# rs232_adapter.net
KiCad netlist of a schematic drawn in EAGLE
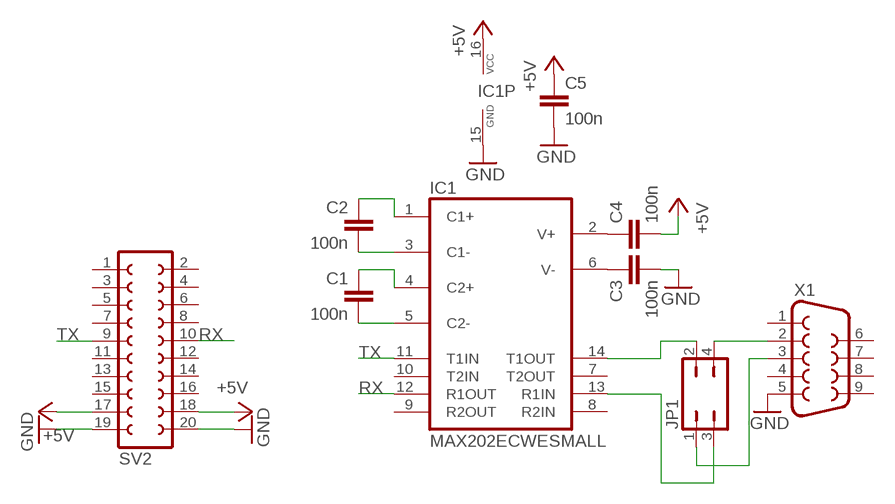
[diagram p0: schematic, sheet 1]

(export (version "E")
  (design (tool "Eeschema 10.0.6"))
  (components
    (comp (ref "C1")
      (value "100n")
      (footprint "eagle-import:C0805")
      (libsource (lib "eagle-import") (part "C-EUC0805"))
    )
    (comp (ref "C2")
      (value "100n")
      (footprint "eagle-import:C0805")
      (libsource (lib "eagle-import") (part "C-EUC0805"))
    )
    (comp (ref "C3")
      (value "100n")
      (footprint "eagle-import:C0805")
      (libsource (lib "eagle-import") (part "C-EUC0805"))
    )
    (comp (ref "C4")
      (value "100n")
      (footprint "eagle-import:C0805")
      (libsource (lib "eagle-import") (part "C-EUC0805"))
    )
    (comp (ref "C5")
      (value "100n")
      (footprint "eagle-import:C0805")
      (libsource (lib "eagle-import") (part "C-EUC0805"))
    )
    (comp (ref "IC1")
      (value "MAX202ECWESMALL")
      (footprint "eagle-import:SO16")
      (libsource (lib "eagle-import") (part "MAX202ECWESMALL"))
    )
    (comp (ref "JP1")
      (value "JP2Q")
      (footprint "eagle-import:JP2Q")
      (libsource (lib "eagle-import") (part "JP2Q"))
    )
    (comp (ref "SV2")
      (value "FE10-2")
      (footprint "eagle-import:FE10-2")
      (libsource (lib "eagle-import") (part "FE10-2"))
    )
    (comp (ref "X1")
      (value "F09HP")
      (footprint "eagle-import:F09HP")
      (libsource (lib "eagle-import") (part "F09HP"))
    )
  )
  (nets
    (net (code "1") (name "+5V") (class "Default")
      (node (ref "C4") (pin "2") (pinfunction "2_2") (pintype "passive"))
      (node (ref "C5") (pin "1") (pinfunction "1_1") (pintype "passive"))
      (node (ref "IC1") (pin "16") (pinfunction "VCC_16") (pintype "power_in"))
      (node (ref "SV2") (pin "17") (pinfunction "17_17") (pintype "passive"))
      (node (ref "SV2") (pin "18") (pinfunction "18_18") (pintype "passive"))
    )
    (net (code "2") (name "/RX") (class "Default")
      (node (ref "IC1") (pin "12") (pinfunction "R1OUT_12") (pintype "output"))
      (node (ref "SV2") (pin "10") (pinfunction "10_10") (pintype "passive"))
    )
    (net (code "3") (name "/TX") (class "Default")
      (node (ref "IC1") (pin "11") (pinfunction "T1IN_11") (pintype "input"))
      (node (ref "SV2") (pin "9") (pinfunction "9_9") (pintype "passive"))
    )
    (net (code "4") (name "GND") (class "Default")
      (node (ref "C3") (pin "2") (pinfunction "2_2") (pintype "passive"))
      (node (ref "C5") (pin "2") (pinfunction "2_2") (pintype "passive"))
      (node (ref "IC1") (pin "15") (pinfunction "GND_15") (pintype "power_in"))
      (node (ref "SV2") (pin "19") (pinfunction "19_19") (pintype "passive"))
      (node (ref "SV2") (pin "20") (pinfunction "20_20") (pintype "passive"))
      (node (ref "X1") (pin "5") (pinfunction "5_5") (pintype "passive"))
    )
    (net (code "5") (name "Net-(IC1A-C1+)") (class "Default")
      (node (ref "C2") (pin "1") (pinfunction "1_1") (pintype "passive"))
      (node (ref "IC1") (pin "1") (pinfunction "C1+_1") (pintype "bidirectional"))
    )
    (net (code "6") (name "Net-(IC1A-C1-)") (class "Default")
      (node (ref "C2") (pin "2") (pinfunction "2_2") (pintype "passive"))
      (node (ref "IC1") (pin "3") (pinfunction "C1-_3") (pintype "bidirectional"))
    )
    (net (code "7") (name "Net-(IC1A-C2+)") (class "Default")
      (node (ref "C1") (pin "1") (pinfunction "1_1") (pintype "passive"))
      (node (ref "IC1") (pin "4") (pinfunction "C2+_4") (pintype "bidirectional"))
    )
    (net (code "8") (name "Net-(IC1A-C2-)") (class "Default")
      (node (ref "C1") (pin "2") (pinfunction "2_2") (pintype "passive"))
      (node (ref "IC1") (pin "5") (pinfunction "C2-_5") (pintype "bidirectional"))
    )
    (net (code "9") (name "Net-(IC1A-R1IN)") (class "Default")
      (node (ref "IC1") (pin "13") (pinfunction "R1IN_13") (pintype "input"))
      (node (ref "JP1") (pin "3") (pinfunction "3_3") (pintype "passive"))
    )
    (net (code "10") (name "Net-(IC1A-T1OUT)") (class "Default")
      (node (ref "IC1") (pin "14") (pinfunction "T1OUT_14") (pintype "output"))
      (node (ref "JP1") (pin "2") (pinfunction "2_2") (pintype "passive"))
    )
    (net (code "11") (name "Net-(IC1A-V+)") (class "Default")
      (node (ref "C4") (pin "1") (pinfunction "1_1") (pintype "passive"))
      (node (ref "IC1") (pin "2") (pinfunction "V+_2") (pintype "bidirectional"))
    )
    (net (code "12") (name "Net-(IC1A-V-)") (class "Default")
      (node (ref "C3") (pin "1") (pinfunction "1_1") (pintype "passive"))
      (node (ref "IC1") (pin "6") (pinfunction "V-_6") (pintype "bidirectional"))
    )
    (net (code "13") (name "Net-(JP1-Pad1)") (class "Default")
      (node (ref "JP1") (pin "1") (pinfunction "1_1") (pintype "passive"))
      (node (ref "X1") (pin "3") (pinfunction "3_3") (pintype "passive"))
    )
    (net (code "14") (name "Net-(JP1-Pad4)") (class "Default")
      (node (ref "JP1") (pin "4") (pinfunction "4_4") (pintype "passive"))
      (node (ref "X1") (pin "2") (pinfunction "2_2") (pintype "passive"))
    )
    (net (code "15") (name "unconnected-(IC1A-R2IN-Pad8)") (class "Default")
      (node (ref "IC1") (pin "8") (pinfunction "R2IN_8") (pintype "input"))
    )
    (net (code "16") (name "unconnected-(IC1A-R2OUT-Pad9)") (class "Default")
      (node (ref "IC1") (pin "9") (pinfunction "R2OUT_9") (pintype "output"))
    )
    (net (code "17") (name "unconnected-(IC1A-T2IN-Pad10)") (class "Default")
      (node (ref "IC1") (pin "10") (pinfunction "T2IN_10") (pintype "input"))
    )
    (net (code "18") (name "unconnected-(IC1A-T2OUT-Pad7)") (class "Default")
      (node (ref "IC1") (pin "7") (pinfunction "T2OUT_7") (pintype "output"))
    )
    (net (code "19") (name "unconnected-(SV2-Pad1)") (class "Default")
      (node (ref "SV2") (pin "1") (pinfunction "1_1") (pintype "passive"))
    )
    (net (code "20") (name "unconnected-(SV2-Pad2)") (class "Default")
      (node (ref "SV2") (pin "2") (pinfunction "2_2") (pintype "passive"))
    )
    (net (code "21") (name "unconnected-(SV2-Pad3)") (class "Default")
      (node (ref "SV2") (pin "3") (pinfunction "3_3") (pintype "passive"))
    )
    (net (code "22") (name "unconnected-(SV2-Pad4)") (class "Default")
      (node (ref "SV2") (pin "4") (pinfunction "4_4") (pintype "passive"))
    )
    (net (code "23") (name "unconnected-(SV2-Pad5)") (class "Default")
      (node (ref "SV2") (pin "5") (pinfunction "5_5") (pintype "passive"))
    )
    (net (code "24") (name "unconnected-(SV2-Pad6)") (class "Default")
      (node (ref "SV2") (pin "6") (pinfunction "6_6") (pintype "passive"))
    )
    (net (code "25") (name "unconnected-(SV2-Pad7)") (class "Default")
      (node (ref "SV2") (pin "7") (pinfunction "7_7") (pintype "passive"))
    )
    (net (code "26") (name "unconnected-(SV2-Pad8)") (class "Default")
      (node (ref "SV2") (pin "8") (pinfunction "8_8") (pintype "passive"))
    )
    (net (code "27") (name "unconnected-(SV2-Pad11)") (class "Default")
      (node (ref "SV2") (pin "11") (pinfunction "11_11") (pintype "passive"))
    )
    (net (code "28") (name "unconnected-(SV2-Pad12)") (class "Default")
      (node (ref "SV2") (pin "12") (pinfunction "12_12") (pintype "passive"))
    )
    (net (code "29") (name "unconnected-(SV2-Pad13)") (class "Default")
      (node (ref "SV2") (pin "13") (pinfunction "13_13") (pintype "passive"))
    )
    (net (code "30") (name "unconnected-(SV2-Pad14)") (class "Default")
      (node (ref "SV2") (pin "14") (pinfunction "14_14") (pintype "passive"))
    )
    (net (code "31") (name "unconnected-(SV2-Pad15)") (class "Default")
      (node (ref "SV2") (pin "15") (pinfunction "15_15") (pintype "passive"))
    )
    (net (code "32") (name "unconnected-(SV2-Pad16)") (class "Default")
      (node (ref "SV2") (pin "16") (pinfunction "16_16") (pintype "passive"))
    )
    (net (code "33") (name "unconnected-(X1-Pad1)") (class "Default")
      (node (ref "X1") (pin "1") (pinfunction "1_1") (pintype "passive"))
    )
    (net (code "34") (name "unconnected-(X1-Pad4)") (class "Default")
      (node (ref "X1") (pin "4") (pinfunction "4_4") (pintype "passive"))
    )
    (net (code "35") (name "unconnected-(X1-Pad6)") (class "Default")
      (node (ref "X1") (pin "6") (pinfunction "6_6") (pintype "passive"))
    )
    (net (code "36") (name "unconnected-(X1-Pad7)") (class "Default")
      (node (ref "X1") (pin "7") (pinfunction "7_7") (pintype "passive"))
    )
    (net (code "37") (name "unconnected-(X1-Pad8)") (class "Default")
      (node (ref "X1") (pin "8") (pinfunction "8_8") (pintype "passive"))
    )
    (net (code "38") (name "unconnected-(X1-Pad9)") (class "Default")
      (node (ref "X1") (pin "9") (pinfunction "9_9") (pintype "passive"))
    )
  )
)
